# Proximidad.net
KiCad netlist of a schematic drawn in Altium Designer
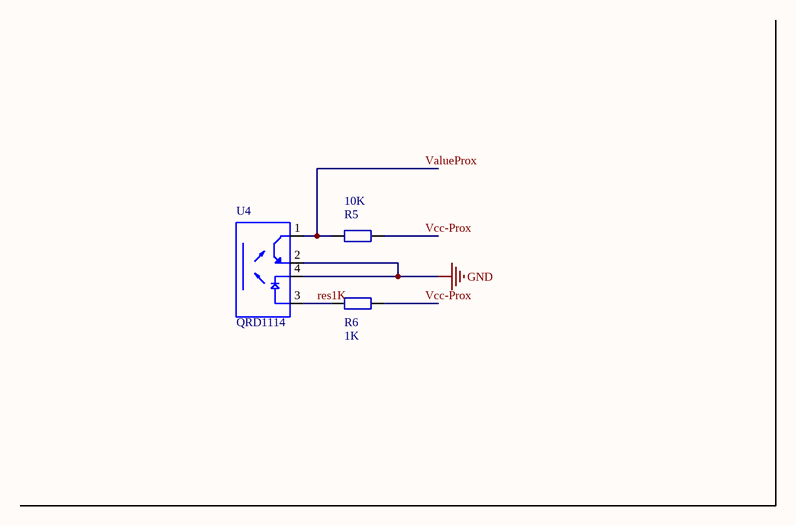
[diagram p0: Proximidad.SchDoc]

(export (version "E")
  (design (tool "Eeschema 10.0.6"))
  (components
    (comp (ref "R5")
      (value "10K")
      (footprint "R1206-0.55")
      (description "Resistor, generic")
      (fields (field (name "Comment") "R"))
      (libsource (lib "IFS_Altium") (part "R"))
    )
    (comp (ref "R6")
      (value "1K")
      (footprint "R1206-0.55")
      (description "Resistor, generic")
      (fields (field (name "Comment") "R"))
      (libsource (lib "IFS_Altium") (part "R"))
    )
    (comp (ref "U4")
      (value "QRD1114")
      (footprint "*ONS_QRD1114")
      (description "Sensor 贸ptico reflectante 0.050 _1.27 mm_ radial - 4 conductores")
      (fields (field (name "DIGI-KEY_PART_NUMBER") "QRD1114-ND") (field (name "MF") "ON Semiconductor"))
      (libsource (lib "QRD1114") (part "QRD1114"))
    )
  )
  (nets
    (net (code "1") (name "/ValueProx") (class "Default")
      (node (ref "R5") (pin "1") (pinfunction "1_1") (pintype "passive"))
      (node (ref "U4") (pin "1") (pinfunction "CT_1") (pintype "passive"))
    )
    (net (code "2") (name "/Vcc-Prox") (class "Default")
      (node (ref "R5") (pin "2") (pinfunction "2_2") (pintype "passive"))
      (node (ref "R6") (pin "2") (pinfunction "2_2") (pintype "passive"))
    )
    (net (code "3") (name "/res1K") (class "Default")
      (node (ref "R6") (pin "1") (pinfunction "1_1") (pintype "passive"))
      (node (ref "U4") (pin "3") (pinfunction "A_3") (pintype "passive"))
    )
    (net (code "4") (name "GND") (class "Default")
      (node (ref "U4") (pin "2") (pinfunction "ET_2") (pintype "passive"))
      (node (ref "U4") (pin "4") (pinfunction "C_4") (pintype "passive"))
    )
  )
)
